# Sheet_buck_boost.net
KiCad netlist of a schematic drawn in Altium Designer
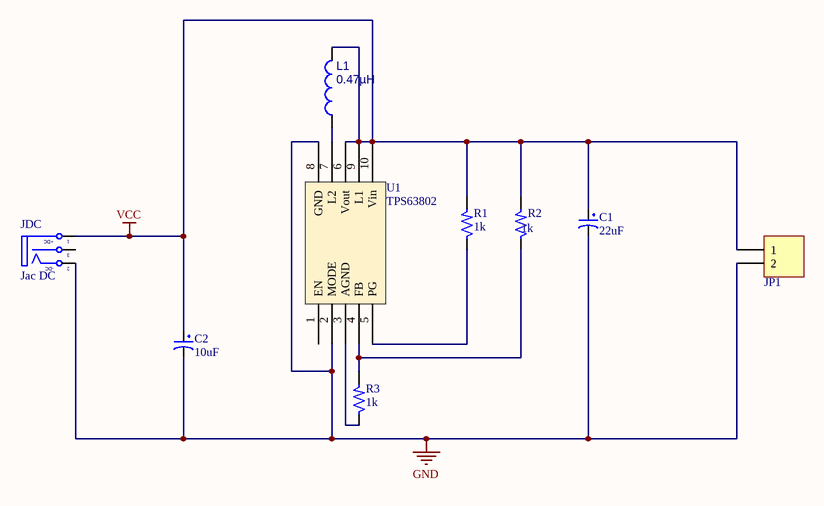
[diagram p0: Sheet_buck&boost.SchDoc]

(export (version "E")
  (design (tool "Eeschema 10.0.6"))
  (components
    (comp (ref "C1")
      (value "22uF")
      (footprint "CP1/2")
      (description "Cap P  0,1uF < 22uF , 16 - 50V")
      (libsource (lib "syhaunguyen") (part "CP1"))
    )
    (comp (ref "C2")
      (value "10uF")
      (footprint "CP1/2")
      (description "Cap P  0,1uF < 22uF , 16 - 50V")
      (libsource (lib "syhaunguyen") (part "CP1"))
    )
    (comp (ref "JDC")
      (value "Jac DC")
      (footprint "DC-IN")
      (description "Jac DC input")
      (libsource (lib "syhaunguyen") (part "DCIN"))
    )
    (comp (ref "JP1")
      (value "Header 2_1")
      (footprint "HED2")
      (description "Header, 2-Pin")
      (fields (field (name "MANUFACTURER") "Generic Components"))
      (libsource (lib "syhaunguyen") (part "Header 2_1"))
    )
    (comp (ref "L1")
      (value "0.47µH")
      (footprint "IND_COILCRAFT_LPS4018")
      (description "Inductor shielded 120uH 300mA LPS4018 SMD")
      (fields (field (name "TOLERANCE") "±20%"))
      (libsource (lib "My library altium") (part "INDC_120u_LPS4018"))
    )
    (comp (ref "R1")
      (value "1k")
      (footprint "SM-RES-1206")
      (description "Resistor 1/4W")
      (libsource (lib "syhaunguyen") (part "R"))
    )
    (comp (ref "R2")
      (value "1k")
      (footprint "SM-RES-1206")
      (description "Resistor 1/4W")
      (libsource (lib "syhaunguyen") (part "R"))
    )
    (comp (ref "R3")
      (value "1k")
      (footprint "SM-RES-1206")
      (description "Resistor 1/4W")
      (libsource (lib "syhaunguyen") (part "R"))
    )
    (comp (ref "U1")
      (value "TPS63802")
      (footprint "TPS63802")
      (description "SMD")
      (libsource (lib "buck&boost (1)") (part "TPS63802"))
    )
  )
  (nets
    (net (code "1") (name "GND") (class "Default")
      (node (ref "C1") (pin "2") (pinfunction "2_2") (pintype "passive"))
      (node (ref "C2") (pin "2") (pinfunction "2_2") (pintype "passive"))
      (node (ref "JDC") (pin "2") (pinfunction "TN_2") (pintype "passive"))
      (node (ref "JP1") (pin "2") (pinfunction "2_2") (pintype "passive"))
      (node (ref "U1") (pin "2") (pinfunction "MODE_2") (pintype "passive"))
      (node (ref "U1") (pin "8") (pinfunction "GND_8") (pintype "passive"))
    )
    (net (code "2") (name "Net-(U1-AGND)") (class "Default")
      (node (ref "R3") (pin "1") (pinfunction "1_1") (pintype "passive"))
      (node (ref "U1") (pin "3") (pinfunction "AGND_3") (pintype "passive"))
    )
    (net (code "3") (name "Net-(U1-FB)") (class "Default")
      (node (ref "R2") (pin "1") (pinfunction "1_1") (pintype "passive"))
      (node (ref "R3") (pin "2") (pinfunction "2_2") (pintype "passive"))
      (node (ref "U1") (pin "4") (pinfunction "FB_4") (pintype "passive"))
    )
    (net (code "4") (name "Net-(U1-L2)") (class "Default")
      (node (ref "L1") (pin "1") (pinfunction "1_1") (pintype "passive"))
      (node (ref "U1") (pin "7") (pinfunction "L2_7") (pintype "passive"))
    )
    (net (code "5") (name "Net-(U1-PG)") (class "Default")
      (node (ref "R1") (pin "1") (pinfunction "1_1") (pintype "passive"))
      (node (ref "U1") (pin "5") (pinfunction "PG_5") (pintype "passive"))
    )
    (net (code "6") (name "VCC") (class "Default")
      (node (ref "C1") (pin "1") (pinfunction "1_1") (pintype "passive"))
      (node (ref "C2") (pin "1") (pinfunction "1_1") (pintype "passive"))
      (node (ref "JDC") (pin "1") (pinfunction "T_1") (pintype "passive"))
      (node (ref "JP1") (pin "1") (pinfunction "1_1") (pintype "passive"))
      (node (ref "L1") (pin "2") (pinfunction "2_2") (pintype "passive"))
      (node (ref "R1") (pin "2") (pinfunction "2_2") (pintype "passive"))
      (node (ref "R2") (pin "2") (pinfunction "2_2") (pintype "passive"))
      (node (ref "U1") (pin "10") (pinfunction "Vin_10") (pintype "passive"))
      (node (ref "U1") (pin "6") (pinfunction "Vout_6") (pintype "passive"))
      (node (ref "U1") (pin "9") (pinfunction "L1_9") (pintype "passive"))
    )
    (net (code "7") (name "unconnected-(JDC-S-Pad3)") (class "Default")
      (node (ref "JDC") (pin "3") (pinfunction "S_3") (pintype "power_in"))
    )
    (net (code "8") (name "unconnected-(U1-EN-Pad1)") (class "Default")
      (node (ref "U1") (pin "1") (pinfunction "EN_1") (pintype "passive"))
    )
  )
)
